# STS_00.net
KiCad netlist of a schematic drawn in Altium Designer
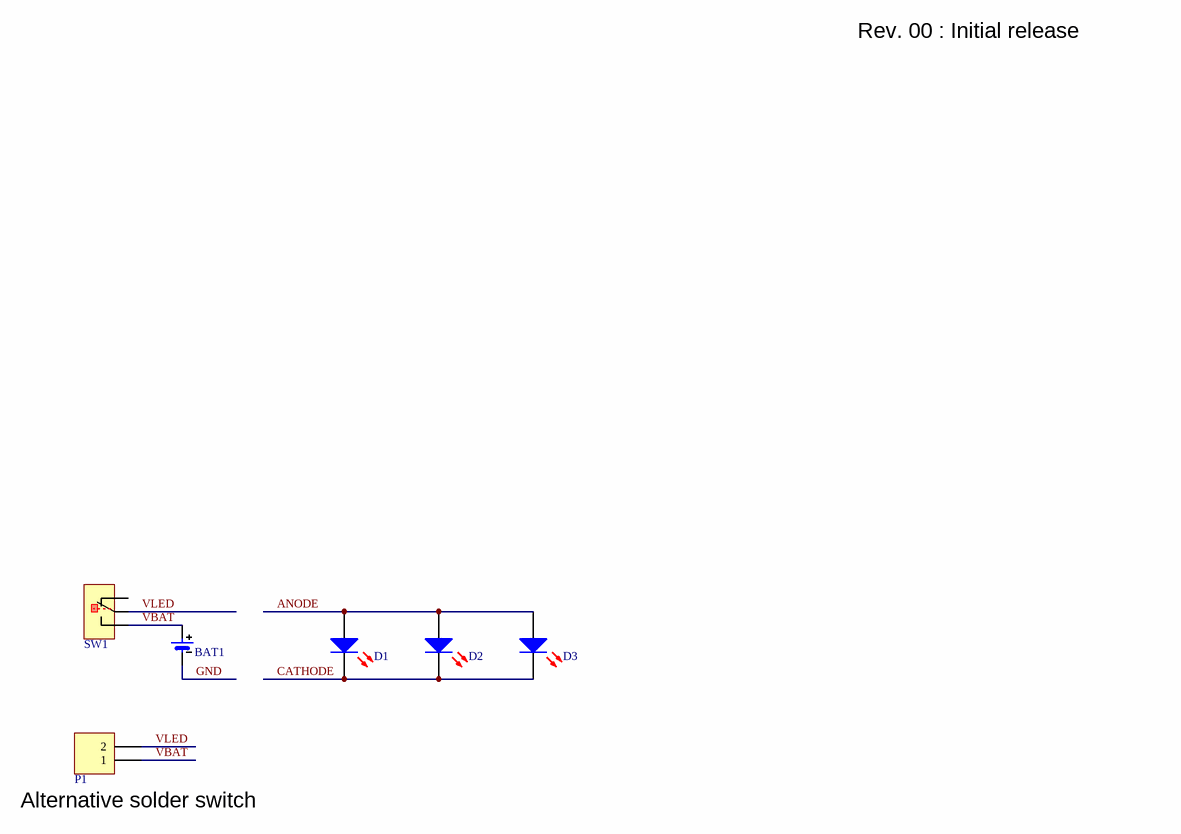
[diagram p0: STS.00.SchDoc]

(export (version "E")
  (design (tool "Eeschema 10.0.6"))
  (components
    (comp (ref "BAT1")
      (value "CR2032 SMD Battery Holder")
      (footprint "BAT_CR2032_KEY_1060")
      (description "=Description")
      (libsource (lib "Phyx_Components") (part "BAT_2"))
    )
    (comp (ref "D1")
      (value "Default 5mm Red LED")
      (footprint "LED_5MM_RD")
      (description "=Description")
      (libsource (lib "Phyx_Components") (part "LED_RED"))
    )
    (comp (ref "D2")
      (value "Default 5mm Red LED")
      (footprint "LED_5MM_RD")
      (description "=Description")
      (libsource (lib "Phyx_Components") (part "LED_RED"))
    )
    (comp (ref "D3")
      (value "Default 5mm Red LED")
      (footprint "LED_5MM_RD")
      (description "=Description")
      (libsource (lib "Phyx_Components") (part "LED_RED"))
    )
    (comp (ref "P1")
      (value "Easy to solder connection")
      (footprint "SOLDER_SW_V_1MM")
      (libsource (lib "Phyx_Components") (part "Header 2"))
    )
    (comp (ref "SW1")
      (value "mini Switch 1 pole double throw right angle")
      (footprint "SK-12D07")
      (description "SW 1P2T micro RA SK-12D07")
      (libsource (lib "Phyx_Components") (part "SW_1P2T"))
    )
  )
  (nets
    (net (code "1") (name "/ANODE") (class "Default")
      (node (ref "D1") (pin "1") (pinfunction "A_1") (pintype "passive"))
      (node (ref "D2") (pin "1") (pinfunction "A_1") (pintype "passive"))
      (node (ref "D3") (pin "1") (pinfunction "A_1") (pintype "passive"))
    )
    (net (code "2") (name "/CATHODE") (class "Default")
      (node (ref "D1") (pin "2") (pinfunction "K_2") (pintype "passive"))
      (node (ref "D2") (pin "2") (pinfunction "K_2") (pintype "passive"))
      (node (ref "D3") (pin "2") (pinfunction "K_2") (pintype "passive"))
    )
    (net (code "3") (name "/GND") (class "Default")
      (node (ref "BAT1") (pin "2") (pinfunction "2_2") (pintype "passive"))
    )
    (net (code "4") (name "/VBAT") (class "Default")
      (node (ref "BAT1") (pin "1") (pinfunction "1_1") (pintype "passive"))
      (node (ref "P1") (pin "1") (pinfunction "1_1") (pintype "passive"))
      (node (ref "SW1") (pin "3") (pinfunction "3_3") (pintype "passive"))
    )
    (net (code "5") (name "/VLED") (class "Default")
      (node (ref "P1") (pin "2") (pinfunction "2_2") (pintype "passive"))
      (node (ref "SW1") (pin "2") (pinfunction "2_2") (pintype "passive"))
    )
    (net (code "6") (name "unconnected-(SW1-Pad1)") (class "Default")
      (node (ref "SW1") (pin "1") (pinfunction "1_1") (pintype "passive"))
    )
  )
)
